# rng_2_0.net
KiCad netlist of a schematic drawn in EAGLE
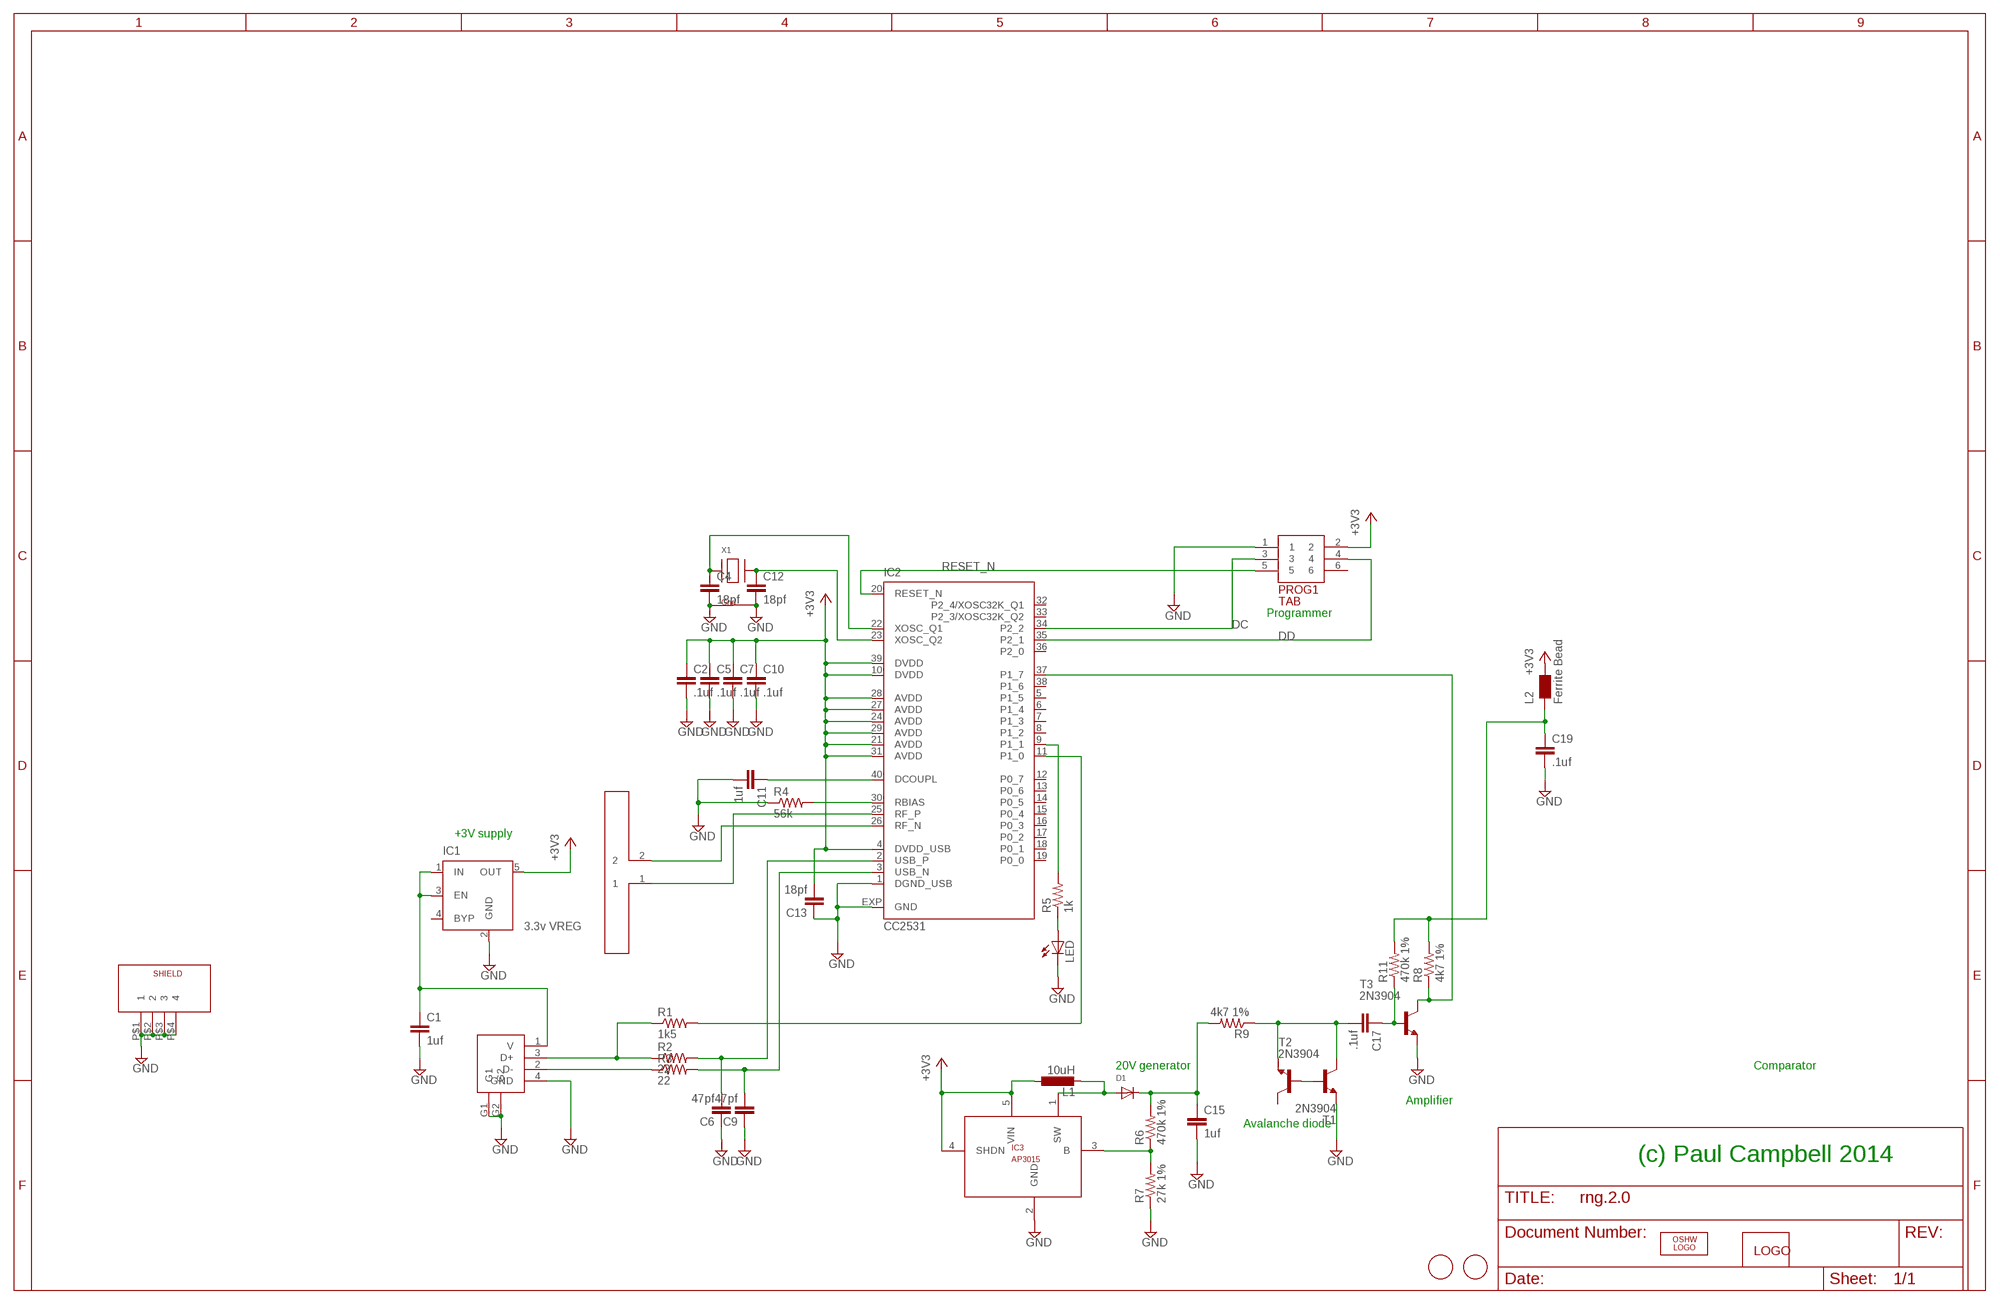
[diagram p0: schematic, sheet 1]

(export (version "E")
  (design (tool "Eeschema 10.0.6"))
  (components
    (comp (ref "C1")
      (value "1uf")
      (footprint "eagle-import:C0603")
      (libsource (lib "eagle-import") (part "C-EUC0603"))
    )
    (comp (ref "C2")
      (value ".1uf")
      (footprint "eagle-import:C0603")
      (libsource (lib "eagle-import") (part "C-EUC0603"))
    )
    (comp (ref "C4")
      (value "18pf")
      (footprint "eagle-import:C0603")
      (libsource (lib "eagle-import") (part "C-EUC0603"))
    )
    (comp (ref "C5")
      (value ".1uf")
      (footprint "eagle-import:C0603K")
      (libsource (lib "eagle-import") (part "C-EUC0603K"))
    )
    (comp (ref "C6")
      (value "47pf")
      (footprint "eagle-import:C0603")
      (libsource (lib "eagle-import") (part "C-EUC0603"))
    )
    (comp (ref "C7")
      (value ".1uf")
      (footprint "eagle-import:C0603")
      (libsource (lib "eagle-import") (part "C-EUC0603"))
    )
    (comp (ref "C9")
      (value "47pf")
      (footprint "eagle-import:C0603")
      (libsource (lib "eagle-import") (part "C-EUC0603"))
    )
    (comp (ref "C10")
      (value ".1uf")
      (footprint "eagle-import:C0603")
      (libsource (lib "eagle-import") (part "C-EUC0603"))
    )
    (comp (ref "C11")
      (value "1uf")
      (footprint "eagle-import:C0603")
      (libsource (lib "eagle-import") (part "C-EUC0603"))
    )
    (comp (ref "C12")
      (value "18pf")
      (footprint "eagle-import:C0603")
      (libsource (lib "eagle-import") (part "C-EUC0603"))
    )
    (comp (ref "C13")
      (value "18pf")
      (footprint "eagle-import:C0603")
      (libsource (lib "eagle-import") (part "C-EUC0603"))
    )
    (comp (ref "C15")
      (value "1uf")
      (footprint "eagle-import:C0603")
      (libsource (lib "eagle-import") (part "C-EUC0603"))
    )
    (comp (ref "C17")
      (value ".1uf")
      (footprint "eagle-import:C0603")
      (libsource (lib "eagle-import") (part "C-EUC0603"))
    )
    (comp (ref "C19")
      (value ".1uf")
      (footprint "eagle-import:C0603")
      (libsource (lib "eagle-import") (part "C-EUC0603"))
    )
    (comp (ref "D1")
      (value "DIODESOD-323F")
      (footprint "eagle-import:SOD-323F")
      (libsource (lib "eagle-import") (part "DIODESOD-323F"))
    )
    (comp (ref "IC1")
      (value "3.3v VREG")
      (footprint "eagle-import:SOT23-5")
      (libsource (lib "eagle-import") (part "MIC5219XX"))
    )
    (comp (ref "IC2")
      (value "CC2531")
      (footprint "eagle-import:RHA_S-PVQFN-N40")
      (fields (field (name "MPN") "CC2531F256RHAT"))
      (libsource (lib "eagle-import") (part "CC2531"))
    )
    (comp (ref "IC3")
      (value "AP3015")
      (footprint "eagle-import:SOT23-5")
      (libsource (lib "eagle-import") (part "AP3105"))
    )
    (comp (ref "L1")
      (value "10uH")
      (footprint "eagle-import:L2012C")
      (libsource (lib "eagle-import") (part "L-EUL2012C"))
    )
    (comp (ref "L2")
      (value "Ferrite Bead")
      (footprint "eagle-import:0603")
      (libsource (lib "eagle-import") (part "WE-CBF_0603"))
    )
    (comp (ref "LED")
      (value "LEDCHIP-LED0805")
      (footprint "eagle-import:CHIP-LED0805")
      (libsource (lib "eagle-import") (part "LEDCHIP-LED0805"))
    )
    (comp (ref "LOGO1")
      (value "OSHW_LOGO_FILLX0100-NT")
      (footprint "eagle-import:OSHW_FILLX100_NOTEXT")
      (libsource (lib "eagle-import") (part "OSHW_LOGO_FILLX0100-NT"))
    )
    (comp (ref "PROG1")
      (value "TAB")
      (footprint "eagle-import:TAG")
      (libsource (lib "eagle-import") (part "TAB"))
    )
    (comp (ref "R1")
      (value "1k5")
      (footprint "eagle-import:R0603")
      (libsource (lib "eagle-import") (part "R-US_R0603"))
    )
    (comp (ref "R2")
      (value "22")
      (footprint "eagle-import:R0603")
      (libsource (lib "eagle-import") (part "R-US_R0603"))
    )
    (comp (ref "R3")
      (value "22")
      (footprint "eagle-import:R0603")
      (libsource (lib "eagle-import") (part "R-US_R0603"))
    )
    (comp (ref "R4")
      (value "56k")
      (footprint "eagle-import:R0603")
      (libsource (lib "eagle-import") (part "R-US_R0603"))
    )
    (comp (ref "R5")
      (value "1k")
      (footprint "eagle-import:R0603")
      (libsource (lib "eagle-import") (part "R-US_R0603"))
    )
    (comp (ref "R6")
      (value "470k 1%")
      (footprint "eagle-import:R0603")
      (libsource (lib "eagle-import") (part "R-US_R0603"))
    )
    (comp (ref "R7")
      (value "27k 1%")
      (footprint "eagle-import:R0603")
      (libsource (lib "eagle-import") (part "R-US_R0603"))
    )
    (comp (ref "R8")
      (value "4k7 1%")
      (footprint "eagle-import:R0603")
      (libsource (lib "eagle-import") (part "R-US_R0603"))
    )
    (comp (ref "R9")
      (value "4k7 1%")
      (footprint "eagle-import:R0603")
      (libsource (lib "eagle-import") (part "R-US_R0603"))
    )
    (comp (ref "R11")
      (value "470k 1%")
      (footprint "eagle-import:R0603")
      (libsource (lib "eagle-import") (part "R-US_R0603"))
    )
    (comp (ref "T1")
      (value "2N3904")
      (footprint "eagle-import:SOT23-BEC")
      (libsource (lib "eagle-import") (part "-NPN-SOT23-BECBCF32"))
    )
    (comp (ref "T2")
      (value "2N3904")
      (footprint "eagle-import:SOT23-BEC")
      (libsource (lib "eagle-import") (part "-NPN-SOT23-BECBCF32"))
    )
    (comp (ref "T3")
      (value "2N3904")
      (footprint "eagle-import:SOT23-BEC")
      (libsource (lib "eagle-import") (part "-NPN-SOT23-BECBCF32"))
    )
    (comp (ref "U$1")
      (value "USB-RAW")
      (footprint "eagle-import:USBY")
      (libsource (lib "eagle-import") (part "USB-RAW"))
    )
    (comp (ref "U$2")
      (value "DIPOLEDIPOLE1")
      (footprint "eagle-import:DIPOLE")
      (libsource (lib "eagle-import") (part "DIPOLEDIPOLE1"))
    )
    (comp (ref "U$3")
      (value "FIDUCIAL")
      (footprint "eagle-import:FIDUCIAL_1MM")
      (libsource (lib "eagle-import") (part "FIDUCIAL"))
    )
    (comp (ref "U$4")
      (value "FIDUCIAL")
      (footprint "eagle-import:FIDUCIAL_1MM")
      (libsource (lib "eagle-import") (part "FIDUCIAL"))
    )
    (comp (ref "U$5")
      (value "MOONBASE-LOGO")
      (footprint "eagle-import:MOONBASE-LOGO")
      (libsource (lib "eagle-import") (part "MOONBASE-LOGO"))
    )
    (comp (ref "U$7")
      (value "SHIELD-NEW")
      (footprint "eagle-import:SHIELD-NEW")
      (libsource (lib "eagle-import") (part "SHIELD-NEW"))
    )
    (comp (ref "X1")
      (value "XTAL-4-3225")
      (footprint "eagle-import:NX3225")
      (libsource (lib "eagle-import") (part "XTAL-4-3225"))
    )
  )
  (nets
    (net (code "1") (name "+3V3") (class "Default")
      (node (ref "C10") (pin "1") (pinfunction "1_1") (pintype "passive"))
      (node (ref "C13") (pin "2") (pinfunction "2_2") (pintype "passive"))
      (node (ref "C2") (pin "1") (pinfunction "1_1") (pintype "passive"))
      (node (ref "C5") (pin "1") (pinfunction "1_1") (pintype "passive"))
      (node (ref "C7") (pin "1") (pinfunction "1_1") (pintype "passive"))
      (node (ref "IC1") (pin "5") (pinfunction "OUT_5") (pintype "output"))
      (node (ref "IC2") (pin "10") (pinfunction "DVDD_10") (pintype "power_in"))
      (node (ref "IC2") (pin "21") (pinfunction "AVDD_21") (pintype "power_in"))
      (node (ref "IC2") (pin "24") (pinfunction "AVDD_24") (pintype "power_in"))
      (node (ref "IC2") (pin "27") (pinfunction "AVDD_27") (pintype "power_in"))
      (node (ref "IC2") (pin "28") (pinfunction "AVDD_28") (pintype "power_in"))
      (node (ref "IC2") (pin "29") (pinfunction "AVDD_29") (pintype "power_in"))
      (node (ref "IC2") (pin "31") (pinfunction "AVDD_31") (pintype "power_in"))
      (node (ref "IC2") (pin "39") (pinfunction "DVDD_39") (pintype "power_in"))
      (node (ref "IC2") (pin "4") (pinfunction "DVDD_USB_4") (pintype "power_in"))
      (node (ref "IC3") (pin "4") (pinfunction "SHDN_4") (pintype "bidirectional"))
      (node (ref "IC3") (pin "5") (pinfunction "VIN_5") (pintype "bidirectional"))
      (node (ref "L1") (pin "1") (pinfunction "1_1") (pintype "passive"))
      (node (ref "L2") (pin "2") (pinfunction "2_2") (pintype "passive"))
      (node (ref "PROG1") (pin "2") (pinfunction "2_2") (pintype "bidirectional"))
    )
    (net (code "2") (name "/DC") (class "Default")
      (node (ref "IC2") (pin "34") (pinfunction "P2_2_34") (pintype "bidirectional"))
      (node (ref "PROG1") (pin "3") (pinfunction "3_3") (pintype "bidirectional"))
    )
    (net (code "3") (name "/DD") (class "Default")
      (node (ref "IC2") (pin "35") (pinfunction "P2_1_35") (pintype "bidirectional"))
      (node (ref "PROG1") (pin "4") (pinfunction "4_4") (pintype "bidirectional"))
    )
    (net (code "4") (name "/RESET_N") (class "Default")
      (node (ref "IC2") (pin "20") (pinfunction "RESET_N_20") (pintype "input"))
      (node (ref "PROG1") (pin "5") (pinfunction "5_5") (pintype "bidirectional"))
    )
    (net (code "5") (name "GND") (class "Default")
      (node (ref "C1") (pin "2") (pinfunction "2_2") (pintype "passive"))
      (node (ref "C10") (pin "2") (pinfunction "2_2") (pintype "passive"))
      (node (ref "C11") (pin "2") (pinfunction "2_2") (pintype "passive"))
      (node (ref "C12") (pin "2") (pinfunction "2_2") (pintype "passive"))
      (node (ref "C13") (pin "1") (pinfunction "1_1") (pintype "passive"))
      (node (ref "C15") (pin "2") (pinfunction "2_2") (pintype "passive"))
      (node (ref "C19") (pin "2") (pinfunction "2_2") (pintype "passive"))
      (node (ref "C2") (pin "2") (pinfunction "2_2") (pintype "passive"))
      (node (ref "C4") (pin "2") (pinfunction "2_2") (pintype "passive"))
      (node (ref "C5") (pin "2") (pinfunction "2_2") (pintype "passive"))
      (node (ref "C6") (pin "1") (pinfunction "1_1") (pintype "passive"))
      (node (ref "C7") (pin "2") (pinfunction "2_2") (pintype "passive"))
      (node (ref "C9") (pin "1") (pinfunction "1_1") (pintype "passive"))
      (node (ref "IC1") (pin "2") (pinfunction "GND_2") (pintype "power_in"))
      (node (ref "IC2") (pin "1") (pinfunction "DGND_USB_1") (pintype "power_in"))
      (node (ref "IC2") (pin "EXP") (pinfunction "GND_EXP") (pintype "passive"))
      (node (ref "IC3") (pin "2") (pinfunction "GND_2") (pintype "bidirectional"))
      (node (ref "LED") (pin "C") (pinfunction "C_C") (pintype "passive"))
      (node (ref "PROG1") (pin "1") (pinfunction "1_1") (pintype "bidirectional"))
      (node (ref "R4") (pin "1") (pinfunction "1_1") (pintype "passive"))
      (node (ref "R7") (pin "1") (pinfunction "1_1") (pintype "passive"))
      (node (ref "T2") (pin "E") (pinfunction "E_E") (pintype "passive"))
      (node (ref "T3") (pin "E") (pinfunction "E_E") (pintype "passive"))
      (node (ref "U$1") (pin "4") (pinfunction "GND_4") (pintype "bidirectional"))
      (node (ref "U$1") (pin "G1") (pinfunction "G1_G1") (pintype "bidirectional"))
      (node (ref "U$1") (pin "G2") (pinfunction "G2_G2") (pintype "bidirectional"))
      (node (ref "U$7") (pin "P$1") (pinfunction "1_P$1") (pintype "bidirectional"))
      (node (ref "U$7") (pin "P$2") (pinfunction "2_P$2") (pintype "bidirectional"))
      (node (ref "U$7") (pin "P$3") (pinfunction "3_P$3") (pintype "bidirectional"))
      (node (ref "U$7") (pin "P$4") (pinfunction "4_P$4") (pintype "bidirectional"))
      (node (ref "X1") (pin "2") (pinfunction "G2_2") (pintype "power_in"))
      (node (ref "X1") (pin "4") (pinfunction "G1_4") (pintype "power_in"))
    )
    (net (code "6") (name "Net-(C15-Pad1)") (class "Default")
      (node (ref "C15") (pin "1") (pinfunction "1_1") (pintype "passive"))
      (node (ref "D1") (pin "C") (pinfunction "C_C") (pintype "passive"))
      (node (ref "R6") (pin "2") (pinfunction "2_2") (pintype "passive"))
      (node (ref "R9") (pin "2") (pinfunction "2_2") (pintype "passive"))
    )
    (net (code "7") (name "Net-(C17-Pad1)") (class "Default")
      (node (ref "C17") (pin "1") (pinfunction "1_1") (pintype "passive"))
      (node (ref "R11") (pin "1") (pinfunction "1_1") (pintype "passive"))
      (node (ref "T3") (pin "B") (pinfunction "B_B") (pintype "passive"))
    )
    (net (code "8") (name "Net-(C17-Pad2)") (class "Default")
      (node (ref "C17") (pin "2") (pinfunction "2_2") (pintype "passive"))
      (node (ref "R9") (pin "1") (pinfunction "1_1") (pintype "passive"))
      (node (ref "T1") (pin "E") (pinfunction "E_E") (pintype "passive"))
      (node (ref "T2") (pin "C") (pinfunction "C_C") (pintype "passive"))
    )
    (net (code "9") (name "Net-(C19-Pad1)") (class "Default")
      (node (ref "C19") (pin "1") (pinfunction "1_1") (pintype "passive"))
      (node (ref "L2") (pin "1") (pinfunction "1_1") (pintype "passive"))
      (node (ref "R11") (pin "2") (pinfunction "2_2") (pintype "passive"))
      (node (ref "R8") (pin "2") (pinfunction "2_2") (pintype "passive"))
    )
    (net (code "10") (name "Net-(IC1-EN)") (class "Default")
      (node (ref "C1") (pin "1") (pinfunction "1_1") (pintype "passive"))
      (node (ref "IC1") (pin "1") (pinfunction "IN_1") (pintype "input"))
      (node (ref "IC1") (pin "3") (pinfunction "EN_3") (pintype "input"))
      (node (ref "U$1") (pin "1") (pinfunction "V_1") (pintype "bidirectional"))
    )
    (net (code "11") (name "Net-(IC2-DCOUPL)") (class "Default")
      (node (ref "C11") (pin "1") (pinfunction "1_1") (pintype "passive"))
      (node (ref "IC2") (pin "40") (pinfunction "DCOUPL_40") (pintype "power_in"))
    )
    (net (code "12") (name "Net-(IC2-P1_0)") (class "Default")
      (node (ref "IC2") (pin "11") (pinfunction "P1_0_11") (pintype "bidirectional"))
      (node (ref "R1") (pin "2") (pinfunction "2_2") (pintype "passive"))
    )
    (net (code "13") (name "Net-(IC2-P1_1)") (class "Default")
      (node (ref "IC2") (pin "9") (pinfunction "P1_1_9") (pintype "bidirectional"))
      (node (ref "R5") (pin "2") (pinfunction "2_2") (pintype "passive"))
    )
    (net (code "14") (name "Net-(IC2-P1_7)") (class "Default")
      (node (ref "IC2") (pin "37") (pinfunction "P1_7_37") (pintype "bidirectional"))
      (node (ref "R8") (pin "1") (pinfunction "1_1") (pintype "passive"))
      (node (ref "T3") (pin "C") (pinfunction "C_C") (pintype "passive"))
    )
    (net (code "15") (name "Net-(IC2-RBIAS)") (class "Default")
      (node (ref "IC2") (pin "30") (pinfunction "RBIAS_30") (pintype "bidirectional"))
      (node (ref "R4") (pin "2") (pinfunction "2_2") (pintype "passive"))
    )
    (net (code "16") (name "Net-(IC2-RF_N)") (class "Default")
      (node (ref "IC2") (pin "26") (pinfunction "RF_N_26") (pintype "bidirectional"))
      (node (ref "U$2") (pin "2") (pinfunction "2_2") (pintype "bidirectional"))
    )
    (net (code "17") (name "Net-(IC2-RF_P)") (class "Default")
      (node (ref "IC2") (pin "25") (pinfunction "RF_P_25") (pintype "bidirectional"))
      (node (ref "U$2") (pin "1") (pinfunction "1_1") (pintype "bidirectional"))
    )
    (net (code "18") (name "Net-(IC2-USB_N)") (class "Default")
      (node (ref "C9") (pin "2") (pinfunction "2_2") (pintype "passive"))
      (node (ref "IC2") (pin "3") (pinfunction "USB_N_3") (pintype "bidirectional"))
      (node (ref "R3") (pin "2") (pinfunction "2_2") (pintype "passive"))
    )
    (net (code "19") (name "Net-(IC2-USB_P)") (class "Default")
      (node (ref "C6") (pin "2") (pinfunction "2_2") (pintype "passive"))
      (node (ref "IC2") (pin "2") (pinfunction "USB_P_2") (pintype "bidirectional"))
      (node (ref "R2") (pin "2") (pinfunction "2_2") (pintype "passive"))
    )
    (net (code "20") (name "Net-(IC2-XOSC_Q1)") (class "Default")
      (node (ref "C4") (pin "1") (pinfunction "1_1") (pintype "passive"))
      (node (ref "IC2") (pin "22") (pinfunction "XOSC_Q1_22") (pintype "bidirectional"))
      (node (ref "X1") (pin "1") (pinfunction "X1_1") (pintype "bidirectional"))
    )
    (net (code "21") (name "Net-(IC2-XOSC_Q2)") (class "Default")
      (node (ref "C12") (pin "1") (pinfunction "1_1") (pintype "passive"))
      (node (ref "IC2") (pin "23") (pinfunction "XOSC_Q2_23") (pintype "bidirectional"))
      (node (ref "X1") (pin "3") (pinfunction "X2_3") (pintype "bidirectional"))
    )
    (net (code "22") (name "Net-(IC3-B)") (class "Default")
      (node (ref "IC3") (pin "3") (pinfunction "B_3") (pintype "bidirectional"))
      (node (ref "R6") (pin "1") (pinfunction "1_1") (pintype "passive"))
      (node (ref "R7") (pin "2") (pinfunction "2_2") (pintype "passive"))
    )
    (net (code "23") (name "Net-(IC3-SW)") (class "Default")
      (node (ref "D1") (pin "A") (pinfunction "A_A") (pintype "passive"))
      (node (ref "IC3") (pin "1") (pinfunction "SW_1") (pintype "bidirectional"))
      (node (ref "L1") (pin "2") (pinfunction "2_2") (pintype "passive"))
    )
    (net (code "24") (name "Net-(LED-PadA)") (class "Default")
      (node (ref "LED") (pin "A") (pinfunction "A_A") (pintype "passive"))
      (node (ref "R5") (pin "1") (pinfunction "1_1") (pintype "passive"))
    )
    (net (code "25") (name "Net-(T1-PadB)") (class "Default")
      (node (ref "T1") (pin "B") (pinfunction "B_B") (pintype "passive"))
      (node (ref "T2") (pin "B") (pinfunction "B_B") (pintype "passive"))
    )
    (net (code "26") (name "Net-(U$1-D+)") (class "Default")
      (node (ref "R1") (pin "1") (pinfunction "1_1") (pintype "passive"))
      (node (ref "R2") (pin "1") (pinfunction "1_1") (pintype "passive"))
      (node (ref "U$1") (pin "3") (pinfunction "D+_3") (pintype "bidirectional"))
    )
    (net (code "27") (name "Net-(U$1-D-)") (class "Default")
      (node (ref "R3") (pin "1") (pinfunction "1_1") (pintype "passive"))
      (node (ref "U$1") (pin "2") (pinfunction "D-_2") (pintype "bidirectional"))
    )
    (net (code "28") (name "unconnected-(IC1-BYP-Pad4)") (class "Default")
      (node (ref "IC1") (pin "4") (pinfunction "BYP_4") (pintype "passive"))
    )
    (net (code "29") (name "unconnected-(IC2-P0_0-Pad19)") (class "Default")
      (node (ref "IC2") (pin "19") (pinfunction "P0_0_19") (pintype "bidirectional"))
    )
    (net (code "30") (name "unconnected-(IC2-P0_1-Pad18)") (class "Default")
      (node (ref "IC2") (pin "18") (pinfunction "P0_1_18") (pintype "bidirectional"))
    )
    (net (code "31") (name "unconnected-(IC2-P0_2-Pad17)") (class "Default")
      (node (ref "IC2") (pin "17") (pinfunction "P0_2_17") (pintype "bidirectional"))
    )
    (net (code "32") (name "unconnected-(IC2-P0_3-Pad16)") (class "Default")
      (node (ref "IC2") (pin "16") (pinfunction "P0_3_16") (pintype "bidirectional"))
    )
    (net (code "33") (name "unconnected-(IC2-P0_4-Pad15)") (class "Default")
      (node (ref "IC2") (pin "15") (pinfunction "P0_4_15") (pintype "bidirectional"))
    )
    (net (code "34") (name "unconnected-(IC2-P0_5-Pad14)") (class "Default")
      (node (ref "IC2") (pin "14") (pinfunction "P0_5_14") (pintype "bidirectional"))
    )
    (net (code "35") (name "unconnected-(IC2-P0_6-Pad13)") (class "Default")
      (node (ref "IC2") (pin "13") (pinfunction "P0_6_13") (pintype "bidirectional"))
    )
    (net (code "36") (name "unconnected-(IC2-P0_7-Pad12)") (class "Default")
      (node (ref "IC2") (pin "12") (pinfunction "P0_7_12") (pintype "bidirectional"))
    )
    (net (code "37") (name "unconnected-(IC2-P1_2-Pad8)") (class "Default")
      (node (ref "IC2") (pin "8") (pinfunction "P1_2_8") (pintype "bidirectional"))
    )
    (net (code "38") (name "unconnected-(IC2-P1_3-Pad7)") (class "Default")
      (node (ref "IC2") (pin "7") (pinfunction "P1_3_7") (pintype "bidirectional"))
    )
    (net (code "39") (name "unconnected-(IC2-P1_4-Pad6)") (class "Default")
      (node (ref "IC2") (pin "6") (pinfunction "P1_4_6") (pintype "bidirectional"))
    )
    (net (code "40") (name "unconnected-(IC2-P1_5-Pad5)") (class "Default")
      (node (ref "IC2") (pin "5") (pinfunction "P1_5_5") (pintype "bidirectional"))
    )
    (net (code "41") (name "unconnected-(IC2-P1_6-Pad38)") (class "Default")
      (node (ref "IC2") (pin "38") (pinfunction "P1_6_38") (pintype "bidirectional"))
    )
    (net (code "42") (name "unconnected-(IC2-P2_0-Pad36)") (class "Default")
      (node (ref "IC2") (pin "36") (pinfunction "P2_0_36") (pintype "bidirectional"))
    )
    (net (code "43") (name "unconnected-(IC2-P2_3{slash}XOSC32K_Q2-Pad33)") (class "Default")
      (node (ref "IC2") (pin "33") (pinfunction "P2_3/XOSC32K_Q2_33") (pintype "bidirectional"))
    )
    (net (code "44") (name "unconnected-(IC2-P2_4{slash}XOSC32K_Q1-Pad32)") (class "Default")
      (node (ref "IC2") (pin "32") (pinfunction "P2_4/XOSC32K_Q1_32") (pintype "bidirectional"))
    )
    (net (code "45") (name "unconnected-(PROG1-Pad6)") (class "Default")
      (node (ref "PROG1") (pin "6") (pinfunction "6_6") (pintype "bidirectional"))
    )
    (net (code "46") (name "unconnected-(T1-PadC)") (class "Default")
      (node (ref "T1") (pin "C") (pinfunction "C_C") (pintype "passive"))
    )
  )
)
